# 7A_SCR_BASED_SSS_SOLAR_CHARGE_CONTROL.net
KiCad netlist of a schematic drawn in Altium Designer
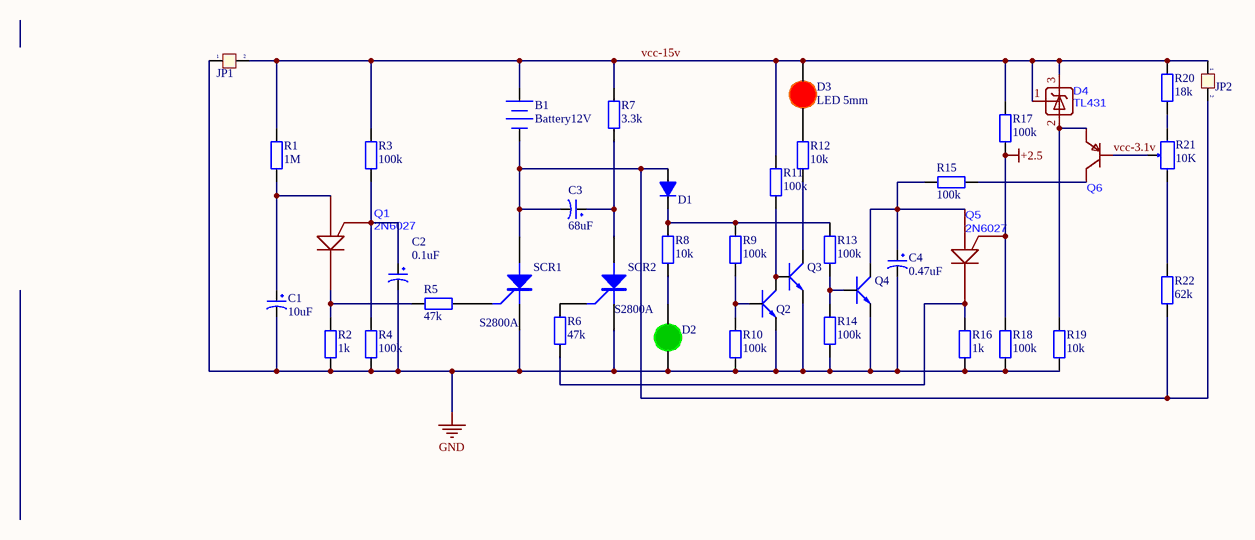
[diagram p0: 7A SCR BASED SSS SOLAR CHARGE CONTROL.SchDoc]

(export (version "E")
  (design (tool "Eeschema 10.0.6"))
  (components
    (comp (ref "B1")
      (value "Battery12V")
      (footprint "HDR1X2")
      (description "Multicell Battery")
      (fields (field (name "PUBLISHER") "Altium Limited"))
      (libsource (lib "Cty1") (part "Battery9V"))
    )
    (comp (ref "C1")
      (value "10uF")
      (footprint "tu hoa 4mm")
      (description "Cắm")
      (libsource (lib "Capacitor") (part "Tu Hoa 10uF 16V 4x7"))
    )
    (comp (ref "C2")
      (value "0.1uF")
      (footprint "tu hoa 5mm")
      (description "Cắm")
      (libsource (lib "Capacitor") (part "Tu Hoa 0.1uF 50V 5x11"))
    )
    (comp (ref "C3")
      (value "68uF")
      (footprint "tu hoa 18mm")
      (description "Cắm")
      (libsource (lib "Capacitor") (part "Tu Hoa 68uF 400V 18x26"))
    )
    (comp (ref "C4")
      (value "0.47uF")
      (footprint "tu hoa 5mm")
      (description "Cắm")
      (libsource (lib "Capacitor") (part "Tu Hoa 0.47uF 50V 5x11"))
    )
    (comp (ref "D1")
      (value "100v")
      (footprint "DIODE 1A")
      (description "Cắm")
      (libsource (lib "Diode") (part "Diode 1N4007"))
    )
    (comp (ref "D2")
      (value "~")
      (footprint "LED-5MM-Green")
      (description "Cắm")
      (libsource (lib "Led") (part "LED 5mm Xanh La"))
    )
    (comp (ref "D3")
      (value "LED 5mm")
      (footprint "LED-5MM-RED")
      (description "Cắm")
      (libsource (lib "Led") (part "LED 5mm Do"))
    )
    (comp (ref "D4")
      (value "TL431")
      (footprint "TO-92-3_L4.9-W3.7-P1.27-L")
      (libsource (lib "MySchlib1") (part "TL431CLPMTL431CLPM"))
    )
    (comp (ref "JP1") (value "Jumper 2") (footprint "J2") (libsource (lib "") (part "JP 2_1_1")))
    (comp (ref "JP2") (value "Jumper 2") (footprint "J2") (libsource (lib "Cty1") (part "JP 2_1")))
    (comp (ref "Q1")
      (value "2N6027")
      (footprint "TO92-INLINE - duplicate")
      (libsource (lib "MySchlib1") (part "2N6027"))
    )
    (comp (ref "Q2")
      (value "~")
      (footprint "TO92")
      (description "NPN transistor EBC")
      (libsource (lib "TranFet") (part "Trans 2N3904"))
    )
    (comp (ref "Q3")
      (value "~")
      (footprint "TO92")
      (description "NPN transistor EBC")
      (libsource (lib "TranFet") (part "Trans 2N3904"))
    )
    (comp (ref "Q4")
      (value "~")
      (footprint "TO92")
      (description "NPN transistor EBC")
      (libsource (lib "TranFet") (part "Trans 2N3904"))
    )
    (comp (ref "Q5")
      (value "2N6027")
      (footprint "TO92-INLINE - duplicate")
      (libsource (lib "MySchlib1") (part "2N6027RLRA_YK"))
    )
    (comp (ref "Q6")
      (value "~")
      (footprint "TO-92-3_L4.9-W3.7-P1.27-L")
      (libsource (lib "MySchlib1") (part "2N3906"))
    )
    (comp (ref "R1")
      (value "1M")
      (footprint "tro vach 1/4w")
      (description "Cắm")
      (libsource (lib "Resistor") (part "Tro Vach 1/4W 5% 1M"))
    )
    (comp (ref "R2")
      (value "1k")
      (footprint "tro vach 1/4w")
      (description "Cắm")
      (libsource (lib "Resistor") (part "Tro Vach 1/4W 5% 1k"))
    )
    (comp (ref "R3")
      (value "100k")
      (footprint "tro vach 1/4w")
      (description "Cắm")
      (libsource (lib "Resistor") (part "Tro Vach 1/4W 5% 100k"))
    )
    (comp (ref "R4")
      (value "100k")
      (footprint "tro vach 1/4w")
      (description "Cắm")
      (libsource (lib "Resistor") (part "Tro Vach 1/4W 5% 100k"))
    )
    (comp (ref "R5")
      (value "47k")
      (footprint "tro vach 1/4w")
      (description "Cắm")
      (libsource (lib "Resistor") (part "Tro Vach 1/4W 5% 47k"))
    )
    (comp (ref "R6")
      (value "47k")
      (footprint "tro vach 1/4w")
      (description "Cắm")
      (libsource (lib "Resistor") (part "Tro Vach 1/4W 5% 47k"))
    )
    (comp (ref "R7")
      (value "3.3k")
      (footprint "tro vach 1/4w")
      (description "Cắm")
      (libsource (lib "Resistor") (part "Tro Vach 1/4W 5% 3.3k"))
    )
    (comp (ref "R8")
      (value "10k")
      (footprint "tro vach 1/4w")
      (description "Căm")
      (libsource (lib "Resistor") (part "Tro Vach 1/4W 5% 10k"))
    )
    (comp (ref "R9")
      (value "100k")
      (footprint "tro vach 1/4w")
      (description "Cắm")
      (libsource (lib "Resistor") (part "Tro Vach 1/4W 5% 100k"))
    )
    (comp (ref "R10")
      (value "100k")
      (footprint "tro vach 1/4w")
      (description "Cắm")
      (libsource (lib "Resistor") (part "Tro Vach 1/4W 5% 100k"))
    )
    (comp (ref "R11")
      (value "100k")
      (footprint "tro vach 1/4w")
      (description "Cắm")
      (libsource (lib "Resistor") (part "Tro Vach 1/4W 5% 100k"))
    )
    (comp (ref "R12")
      (value "10k")
      (footprint "tro vach 1/4w")
      (description "Căm")
      (libsource (lib "Resistor") (part "Tro Vach 1/4W 5% 10k"))
    )
    (comp (ref "R13")
      (value "100k")
      (footprint "tro vach 1/4w")
      (description "Cắm")
      (libsource (lib "Resistor") (part "Tro Vach 1/4W 5% 100k"))
    )
    (comp (ref "R14")
      (value "100k")
      (footprint "tro vach 1/4w")
      (description "Cắm")
      (libsource (lib "Resistor") (part "Tro Vach 1/4W 5% 100k"))
    )
    (comp (ref "R15")
      (value "100k")
      (footprint "tro vach 1/4w")
      (description "Cắm")
      (libsource (lib "Resistor") (part "Tro Vach 1/4W 5% 100k"))
    )
    (comp (ref "R16")
      (value "1k")
      (footprint "tro vach 1/4w")
      (description "Cắm")
      (libsource (lib "Resistor") (part "Tro Vach 1/4W 5% 1k"))
    )
    (comp (ref "R17")
      (value "100k")
      (footprint "tro vach 1/4w")
      (description "Cắm")
      (libsource (lib "Resistor") (part "Tro Vach 1/4W 5% 100k"))
    )
    (comp (ref "R18")
      (value "100k")
      (footprint "tro vach 1/4w")
      (description "Cắm")
      (libsource (lib "Resistor") (part "Tro Vach 1/4W 5% 100k"))
    )
    (comp (ref "R19")
      (value "10k")
      (footprint "tro vach 1/4w")
      (description "Căm")
      (libsource (lib "Resistor") (part "Tro Vach 1/4W 5% 10k"))
    )
    (comp (ref "R20")
      (value "18k")
      (footprint "tro vach 1/4w")
      (description "Cắm")
      (libsource (lib "Resistor") (part "Tro Vach 1/4W 5% 18k"))
    )
    (comp (ref "R21")
      (value "10K")
      (footprint "Bien Tro Vi Chinh Dung")
      (description "Cắm")
      (libsource (lib "Resistor") (part "Bien Tro Tinh Chinh 10K Dung"))
    )
    (comp (ref "R22")
      (value "62k")
      (footprint "tro vach 1/4w")
      (description "Cắm")
      (libsource (lib "Resistor") (part "Tro Vach 1/4W 5% 68k"))
    )
    (comp (ref "SCR1")
      (value "S2800A")
      (footprint "TO92-INLINE - duplicate")
      (libsource (lib "Cty1") (part "SCR"))
    )
    (comp (ref "SCR2")
      (value "S2800A")
      (footprint "TO92-INLINE - duplicate")
      (libsource (lib "Cty1") (part "SCR"))
    )
  )
  (nets
    (net (code "1") (name "+2.5") (class "Default")
      (node (ref "Q5") (pin "2") (pinfunction "G_2") (pintype "passive"))
      (node (ref "R17") (pin "1") (pinfunction "1_1") (pintype "passive"))
      (node (ref "R18") (pin "2") (pinfunction "2_2") (pintype "passive"))
    )
    (net (code "2") (name "/vcc-3.1v") (class "Default")
      (node (ref "Q6") (pin "2") (pinfunction "2_2") (pintype "passive"))
      (node (ref "R21") (pin "2") (pinfunction "2_2") (pintype "passive"))
    )
    (net (code "3") (name "/vcc-15v") (class "Default")
      (node (ref "B1") (pin "1") (pinfunction "+_1") (pintype "passive"))
      (node (ref "D3") (pin "1") (pinfunction "A_1") (pintype "passive"))
      (node (ref "D4") (pin "1") (pinfunction "R_1") (pintype "passive"))
      (node (ref "D4") (pin "3") (pinfunction "K_3") (pintype "passive"))
      (node (ref "JP1") (pin "2") (pinfunction "2_2") (pintype "passive"))
      (node (ref "JP2") (pin "1") (pinfunction "1_1") (pintype "passive"))
      (node (ref "R1") (pin "2") (pinfunction "2_2") (pintype "passive"))
      (node (ref "R11") (pin "2") (pinfunction "2_2") (pintype "passive"))
      (node (ref "R17") (pin "2") (pinfunction "2_2") (pintype "passive"))
      (node (ref "R20") (pin "2") (pinfunction "2_2") (pintype "passive"))
      (node (ref "R3") (pin "2") (pinfunction "2_2") (pintype "passive"))
      (node (ref "R7") (pin "2") (pinfunction "2_2") (pintype "passive"))
    )
    (net (code "4") (name "GND") (class "Default")
      (node (ref "C1") (pin "2") (pinfunction "2_2") (pintype "passive"))
      (node (ref "C2") (pin "2") (pinfunction "2_2") (pintype "passive"))
      (node (ref "C4") (pin "2") (pinfunction "2_2") (pintype "passive"))
      (node (ref "D2") (pin "2") (pinfunction "K_2") (pintype "passive"))
      (node (ref "JP1") (pin "1") (pinfunction "1_1") (pintype "passive"))
      (node (ref "Q2") (pin "1") (pinfunction "E_1") (pintype "passive"))
      (node (ref "Q3") (pin "1") (pinfunction "E_1") (pintype "passive"))
      (node (ref "Q4") (pin "1") (pinfunction "E_1") (pintype "passive"))
      (node (ref "R10") (pin "1") (pinfunction "1_1") (pintype "passive"))
      (node (ref "R14") (pin "1") (pinfunction "1_1") (pintype "passive"))
      (node (ref "R16") (pin "1") (pinfunction "1_1") (pintype "passive"))
      (node (ref "R18") (pin "1") (pinfunction "1_1") (pintype "passive"))
      (node (ref "R19") (pin "1") (pinfunction "1_1") (pintype "passive"))
      (node (ref "R2") (pin "1") (pinfunction "1_1") (pintype "passive"))
      (node (ref "R4") (pin "1") (pinfunction "1_1") (pintype "passive"))
      (node (ref "SCR1") (pin "2") (pinfunction "K_2") (pintype "passive"))
      (node (ref "SCR2") (pin "2") (pinfunction "K_2") (pintype "passive"))
    )
    (net (code "5") (name "Net-(B1--)") (class "Default")
      (node (ref "B1") (pin "2") (pinfunction "-_2") (pintype "passive"))
      (node (ref "C3") (pin "2") (pinfunction "2_2") (pintype "passive"))
      (node (ref "D1") (pin "1") (pinfunction "A_1") (pintype "passive"))
      (node (ref "JP2") (pin "2") (pinfunction "2_2") (pintype "passive"))
      (node (ref "R22") (pin "1") (pinfunction "1_1") (pintype "passive"))
      (node (ref "SCR1") (pin "1") (pinfunction "A_1") (pintype "passive"))
    )
    (net (code "6") (name "Net-(D1-K)") (class "Default")
      (node (ref "D1") (pin "2") (pinfunction "K_2") (pintype "passive"))
      (node (ref "R13") (pin "2") (pinfunction "2_2") (pintype "passive"))
      (node (ref "R8") (pin "2") (pinfunction "2_2") (pintype "passive"))
      (node (ref "R9") (pin "2") (pinfunction "2_2") (pintype "passive"))
    )
    (net (code "7") (name "Net-(D2-A)") (class "Default")
      (node (ref "D2") (pin "1") (pinfunction "A_1") (pintype "passive"))
      (node (ref "R8") (pin "1") (pinfunction "1_1") (pintype "passive"))
    )
    (net (code "8") (name "Net-(D3-K)") (class "Default")
      (node (ref "D3") (pin "2") (pinfunction "K_2") (pintype "passive"))
      (node (ref "R12") (pin "2") (pinfunction "2_2") (pintype "passive"))
    )
    (net (code "9") (name "Net-(D4-A)") (class "Default")
      (node (ref "D4") (pin "2") (pinfunction "A_2") (pintype "passive"))
      (node (ref "Q6") (pin "1") (pinfunction "1_1") (pintype "passive"))
      (node (ref "R19") (pin "2") (pinfunction "2_2") (pintype "passive"))
    )
    (net (code "10") (name "Net-(Q1-A)") (class "Default")
      (node (ref "C1") (pin "1") (pinfunction "1_1") (pintype "passive"))
      (node (ref "Q1") (pin "1") (pinfunction "A_1") (pintype "passive"))
      (node (ref "R1") (pin "1") (pinfunction "1_1") (pintype "passive"))
    )
    (net (code "11") (name "Net-(Q1-G)") (class "Default")
      (node (ref "C2") (pin "1") (pinfunction "1_1") (pintype "passive"))
      (node (ref "Q1") (pin "2") (pinfunction "G_2") (pintype "passive"))
      (node (ref "R3") (pin "1") (pinfunction "1_1") (pintype "passive"))
      (node (ref "R4") (pin "2") (pinfunction "2_2") (pintype "passive"))
    )
    (net (code "12") (name "Net-(Q1-K)") (class "Default")
      (node (ref "Q1") (pin "3") (pinfunction "K_3") (pintype "passive"))
      (node (ref "R2") (pin "2") (pinfunction "2_2") (pintype "passive"))
      (node (ref "R5") (pin "1") (pinfunction "1_1") (pintype "passive"))
    )
    (net (code "13") (name "Net-(Q2-B)") (class "Default")
      (node (ref "Q2") (pin "2") (pinfunction "B_2") (pintype "passive"))
      (node (ref "R10") (pin "2") (pinfunction "2_2") (pintype "passive"))
      (node (ref "R9") (pin "1") (pinfunction "1_1") (pintype "passive"))
    )
    (net (code "14") (name "Net-(Q2-C)") (class "Default")
      (node (ref "Q2") (pin "3") (pinfunction "C_3") (pintype "passive"))
      (node (ref "Q3") (pin "2") (pinfunction "B_2") (pintype "passive"))
      (node (ref "R11") (pin "1") (pinfunction "1_1") (pintype "passive"))
    )
    (net (code "15") (name "Net-(Q3-C)") (class "Default")
      (node (ref "Q3") (pin "3") (pinfunction "C_3") (pintype "passive"))
      (node (ref "R12") (pin "1") (pinfunction "1_1") (pintype "passive"))
    )
    (net (code "16") (name "Net-(Q4-B)") (class "Default")
      (node (ref "Q4") (pin "2") (pinfunction "B_2") (pintype "passive"))
      (node (ref "R13") (pin "1") (pinfunction "1_1") (pintype "passive"))
      (node (ref "R14") (pin "2") (pinfunction "2_2") (pintype "passive"))
    )
    (net (code "17") (name "Net-(Q4-C)") (class "Default")
      (node (ref "C4") (pin "1") (pinfunction "1_1") (pintype "passive"))
      (node (ref "Q4") (pin "3") (pinfunction "C_3") (pintype "passive"))
      (node (ref "Q5") (pin "1") (pinfunction "A_1") (pintype "passive"))
      (node (ref "R15") (pin "2") (pinfunction "2_2") (pintype "passive"))
    )
    (net (code "18") (name "Net-(Q5-K)") (class "Default")
      (node (ref "Q5") (pin "3") (pinfunction "K_3") (pintype "passive"))
      (node (ref "R16") (pin "2") (pinfunction "2_2") (pintype "passive"))
      (node (ref "R6") (pin "1") (pinfunction "1_1") (pintype "passive"))
    )
    (net (code "19") (name "Net-(Q6-Pad3)") (class "Default")
      (node (ref "Q6") (pin "3") (pinfunction "3_3") (pintype "passive"))
      (node (ref "R15") (pin "1") (pinfunction "1_1") (pintype "passive"))
    )
    (net (code "20") (name "Net-(R20-Pad1)") (class "Default")
      (node (ref "R20") (pin "1") (pinfunction "1_1") (pintype "passive"))
      (node (ref "R21") (pin "3") (pinfunction "3_3") (pintype "passive"))
    )
    (net (code "21") (name "Net-(R21-Pad1)") (class "Default")
      (node (ref "R21") (pin "1") (pinfunction "1_1") (pintype "passive"))
      (node (ref "R22") (pin "2") (pinfunction "2_2") (pintype "passive"))
    )
    (net (code "22") (name "Net-(SCR1-G)") (class "Default")
      (node (ref "R5") (pin "2") (pinfunction "2_2") (pintype "passive"))
      (node (ref "SCR1") (pin "3") (pinfunction "G_3") (pintype "passive"))
    )
    (net (code "23") (name "Net-(SCR2-A)") (class "Default")
      (node (ref "C3") (pin "1") (pinfunction "1_1") (pintype "passive"))
      (node (ref "R7") (pin "1") (pinfunction "1_1") (pintype "passive"))
      (node (ref "SCR2") (pin "1") (pinfunction "A_1") (pintype "passive"))
    )
    (net (code "24") (name "Net-(SCR2-G)") (class "Default")
      (node (ref "R6") (pin "2") (pinfunction "2_2") (pintype "passive"))
      (node (ref "SCR2") (pin "3") (pinfunction "G_3") (pintype "passive"))
    )
  )
)
